# Battery_pack.net
KiCad netlist of a schematic drawn in EAGLE
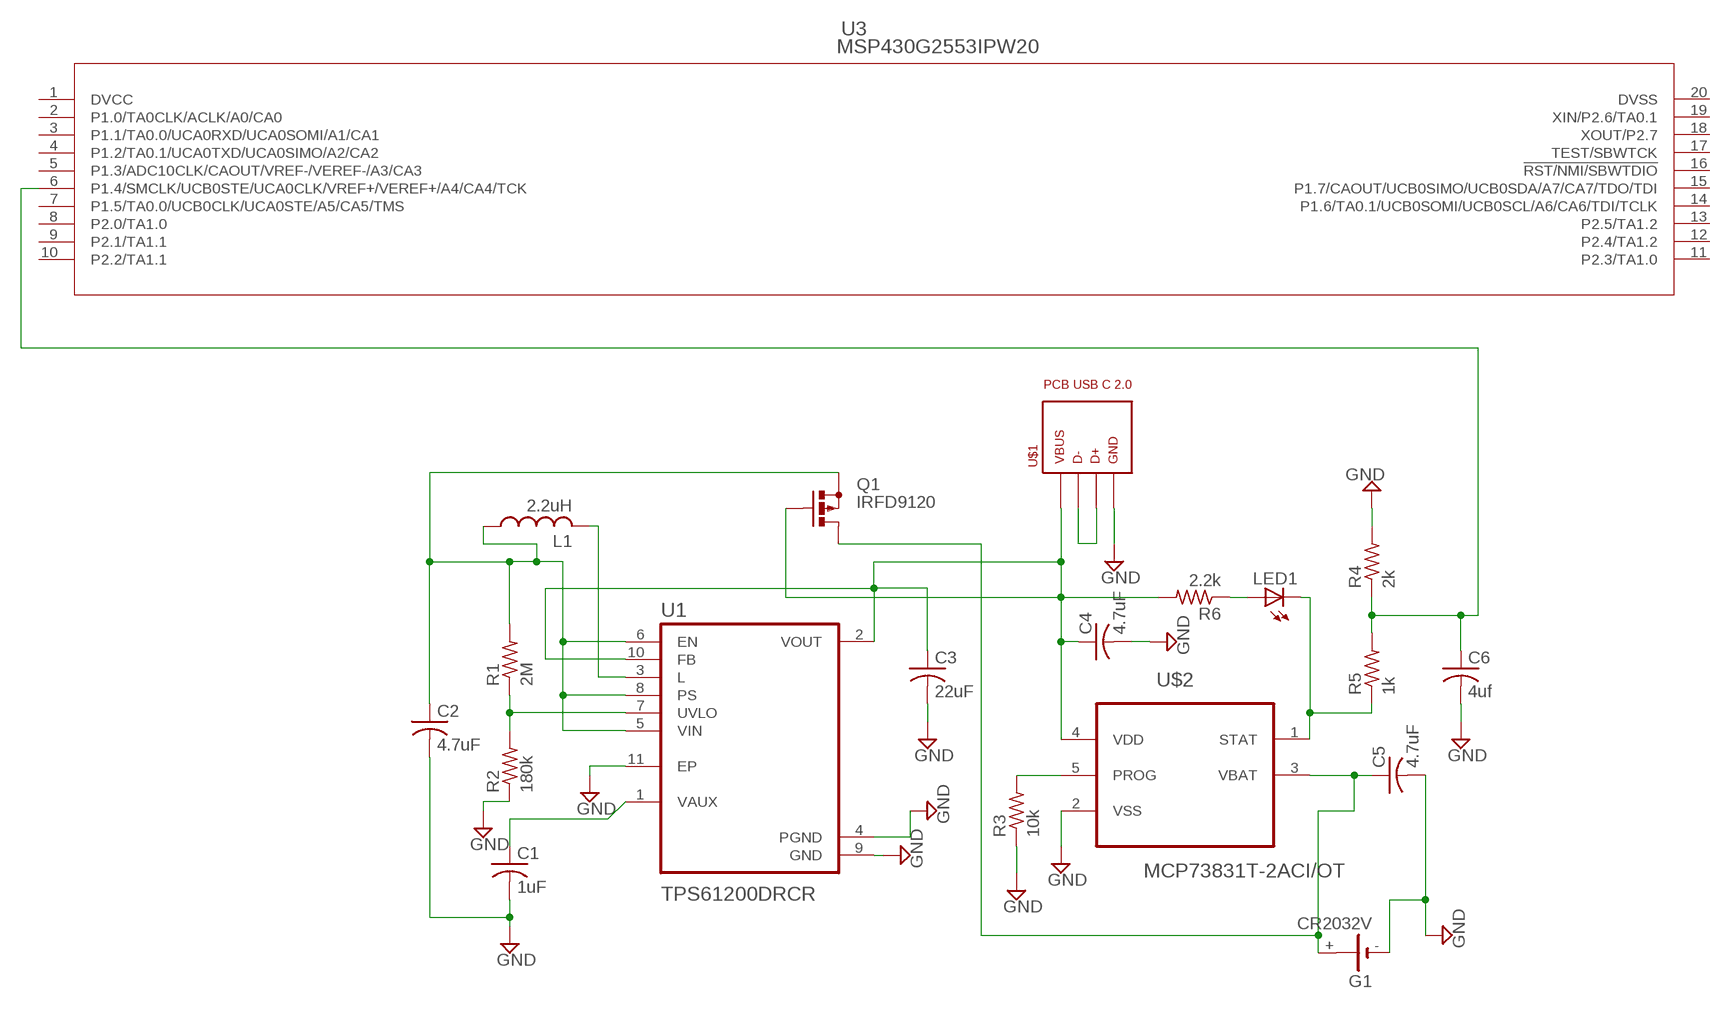
[diagram p0: schematic, sheet 1]

(export (version "E")
  (design (tool "Eeschema 10.0.6"))
  (components
    (comp (ref "C1")
      (value "1uF")
      (footprint "eagle-import:C150-064X183")
      (libsource (lib "eagle-import") (part "C-US150-064X183"))
    )
    (comp (ref "C2")
      (value "4.7uF")
      (footprint "eagle-import:C150-064X183")
      (libsource (lib "eagle-import") (part "C-US150-064X183"))
    )
    (comp (ref "C3")
      (value "22uF")
      (footprint "eagle-import:C150-064X183")
      (libsource (lib "eagle-import") (part "C-US150-064X183"))
    )
    (comp (ref "C4")
      (value "4.7uF")
      (footprint "eagle-import:C150-064X183")
      (libsource (lib "eagle-import") (part "C-US150-064X183"))
    )
    (comp (ref "C5")
      (value "4.7uF")
      (footprint "eagle-import:C150-064X183")
      (libsource (lib "eagle-import") (part "C-US150-064X183"))
    )
    (comp (ref "C6")
      (value "4uf")
      (footprint "eagle-import:C150-064X183")
      (libsource (lib "eagle-import") (part "C-US150-064X183"))
    )
    (comp (ref "G1")
      (value "CR2032V")
      (footprint "eagle-import:CR2032V")
      (libsource (lib "eagle-import") (part "CR2032V"))
    )
    (comp (ref "L1")
      (value "2.2uH")
      (footprint "eagle-import:0207_15")
      (libsource (lib "eagle-import") (part "L-US0207/15"))
    )
    (comp (ref "LED1")
      (value "LEDB155")
      (footprint "eagle-import:Q62902-B155")
      (libsource (lib "eagle-import") (part "LEDB155"))
    )
    (comp (ref "Q1")
      (value "IRFD9120")
      (footprint "eagle-import:C370-01")
      (libsource (lib "eagle-import") (part "IRFD9120"))
    )
    (comp (ref "R1")
      (value "2M")
      (footprint "eagle-import:0207_15")
      (libsource (lib "eagle-import") (part "R-US_0207/15"))
    )
    (comp (ref "R2")
      (value "180k")
      (footprint "eagle-import:0207_15")
      (libsource (lib "eagle-import") (part "R-US_0207/15"))
    )
    (comp (ref "R3")
      (value "10k")
      (footprint "eagle-import:0207_15")
      (libsource (lib "eagle-import") (part "R-US_0207/15"))
    )
    (comp (ref "R4")
      (value "2k")
      (footprint "eagle-import:0207_15")
      (libsource (lib "eagle-import") (part "R-US_0207/15"))
    )
    (comp (ref "R5")
      (value "1k")
      (footprint "eagle-import:0207_15")
      (libsource (lib "eagle-import") (part "R-US_0207/15"))
    )
    (comp (ref "R6")
      (value "2.2k")
      (footprint "eagle-import:0207_15")
      (libsource (lib "eagle-import") (part "R-US_0207/15"))
    )
    (comp (ref "U$1")
      (value "PCB_USB_C_2.0DS_1")
      (footprint "eagle-import:USB_TYPE_C_DS_1")
      (libsource (lib "eagle-import") (part "PCB_USB_C_2.0DS_1"))
    )
    (comp (ref "U$2")
      (value "MCP73831T-2ACI/OT")
      (footprint "eagle-import:SOT95P280X145-5N")
      (fields (field (name "MF") "Microchip"))
      (libsource (lib "eagle-import") (part "MCP73831T-2ACI/OT"))
    )
    (comp (ref "U1")
      (value "TPS61200DRCR")
      (footprint "eagle-import:VREG_V62_16624-01YE")
      (fields (field (name "MF") "Texas Instruments"))
      (libsource (lib "eagle-import") (part "TPS61200DRCR"))
    )
    (comp (ref "U3")
      (value "MSP430G2553IPW20")
      (footprint "eagle-import:PW20")
      (fields
        (field (name "GENERIC_PART_NUMBER") "MSP430G2553")
        (field (name "MANUFACTURER") "Texas Instruments")
      )
      (libsource (lib "eagle-import") (part "MSP430G2553IPW20"))
    )
  )
  (nets
    (net (code "1") (name "/DVCC") (class "Default")
      (node (ref "U3") (pin "1") (pinfunction "DVCC_1") (pintype "power_in"))
    )
    (net (code "2") (name "/DVSS") (class "Default")
      (node (ref "U3") (pin "20") (pinfunction "DVSS_20") (pintype "power_in"))
    )
    (net (code "3") (name "GND") (class "Default")
      (node (ref "C1") (pin "2") (pinfunction "2_2") (pintype "passive"))
      (node (ref "C2") (pin "2") (pinfunction "2_2") (pintype "passive"))
      (node (ref "C3") (pin "2") (pinfunction "2_2") (pintype "passive"))
      (node (ref "C4") (pin "2") (pinfunction "2_2") (pintype "passive"))
      (node (ref "C5") (pin "2") (pinfunction "2_2") (pintype "passive"))
      (node (ref "C6") (pin "2") (pinfunction "2_2") (pintype "passive"))
      (node (ref "G1") (pin "-") (pinfunction "-_-") (pintype "passive"))
      (node (ref "R2") (pin "1") (pinfunction "1_1") (pintype "passive"))
      (node (ref "R3") (pin "1") (pinfunction "1_1") (pintype "passive"))
      (node (ref "R4") (pin "2") (pinfunction "2_2") (pintype "passive"))
      (node (ref "U$1") (pin "A1") (pinfunction "GND_A1") (pintype "bidirectional"))
      (node (ref "U$1") (pin "A12") (pinfunction "GND_A12") (pintype "bidirectional"))
      (node (ref "U$1") (pin "B1") (pinfunction "GND_B1") (pintype "bidirectional"))
      (node (ref "U$1") (pin "B12") (pinfunction "GND_B12") (pintype "bidirectional"))
      (node (ref "U$2") (pin "2") (pinfunction "VSS_2") (pintype "power_in"))
      (node (ref "U1") (pin "11") (pinfunction "EP_11") (pintype "bidirectional"))
      (node (ref "U1") (pin "4") (pinfunction "PGND_4") (pintype "power_in"))
      (node (ref "U1") (pin "9") (pinfunction "GND_9") (pintype "power_in"))
    )
    (net (code "4") (name "Net-(LED1-C)") (class "Default")
      (node (ref "LED1") (pin "K") (pinfunction "C_K") (pintype "passive"))
      (node (ref "R5") (pin "1") (pinfunction "1_1") (pintype "passive"))
      (node (ref "U$2") (pin "1") (pinfunction "STAT_1") (pintype "output"))
    )
    (net (code "5") (name "Net-(LED1-PadA)") (class "Default")
      (node (ref "LED1") (pin "A") (pinfunction "A_A") (pintype "passive"))
      (node (ref "R6") (pin "1") (pinfunction "1_1") (pintype "passive"))
    )
    (net (code "6") (name "Net-(U$1-D+-PadA6)") (class "Default")
      (node (ref "U$1") (pin "A6") (pinfunction "D+_A6") (pintype "bidirectional"))
      (node (ref "U$1") (pin "A7") (pinfunction "D-_A7") (pintype "bidirectional"))
      (node (ref "U$1") (pin "B6") (pinfunction "D+_B6") (pintype "bidirectional"))
      (node (ref "U$1") (pin "B7") (pinfunction "D-_B7") (pintype "bidirectional"))
    )
    (net (code "7") (name "Net-(U$2-PROG)") (class "Default")
      (node (ref "R3") (pin "2") (pinfunction "2_2") (pintype "passive"))
      (node (ref "U$2") (pin "5") (pinfunction "PROG_5") (pintype "input"))
    )
    (net (code "8") (name "Net-(U$2-VBAT)") (class "Default")
      (node (ref "C5") (pin "1") (pinfunction "1_1") (pintype "passive"))
      (node (ref "G1") (pin "+") (pinfunction "+_+") (pintype "passive"))
      (node (ref "Q1") (pin "D") (pinfunction "D_D") (pintype "passive"))
      (node (ref "Q1") (pin "D1") (pinfunction "D_D1") (pintype "passive"))
      (node (ref "U$2") (pin "3") (pinfunction "VBAT_3") (pintype "output"))
    )
    (net (code "9") (name "Net-(U$2-VDD)") (class "Default")
      (node (ref "C3") (pin "1") (pinfunction "1_1") (pintype "passive"))
      (node (ref "C4") (pin "1") (pinfunction "1_1") (pintype "passive"))
      (node (ref "Q1") (pin "G") (pinfunction "G_G") (pintype "passive"))
      (node (ref "R6") (pin "2") (pinfunction "2_2") (pintype "passive"))
      (node (ref "U$1") (pin "A4") (pinfunction "VBUS_A4") (pintype "bidirectional"))
      (node (ref "U$1") (pin "A9") (pinfunction "VBUS_A9") (pintype "bidirectional"))
      (node (ref "U$1") (pin "B4") (pinfunction "VBUS_B4") (pintype "bidirectional"))
      (node (ref "U$1") (pin "B9") (pinfunction "VBUS_B9") (pintype "bidirectional"))
      (node (ref "U$2") (pin "4") (pinfunction "VDD_4") (pintype "power_in"))
      (node (ref "U1") (pin "10") (pinfunction "FB_10") (pintype "input"))
      (node (ref "U1") (pin "2") (pinfunction "VOUT_2") (pintype "output"))
    )
    (net (code "10") (name "Net-(U1-EN)") (class "Default")
      (node (ref "C2") (pin "1") (pinfunction "1_1") (pintype "passive"))
      (node (ref "L1") (pin "1") (pinfunction "1_1") (pintype "passive"))
      (node (ref "Q1") (pin "S") (pinfunction "S_S") (pintype "passive"))
      (node (ref "R1") (pin "2") (pinfunction "2_2") (pintype "passive"))
      (node (ref "U1") (pin "5") (pinfunction "VIN_5") (pintype "input"))
      (node (ref "U1") (pin "6") (pinfunction "EN_6") (pintype "input"))
      (node (ref "U1") (pin "8") (pinfunction "PS_8") (pintype "input"))
    )
    (net (code "11") (name "Net-(U1-L)") (class "Default")
      (node (ref "L1") (pin "2") (pinfunction "2_2") (pintype "passive"))
      (node (ref "U1") (pin "3") (pinfunction "L_3") (pintype "input"))
    )
    (net (code "12") (name "Net-(U1-UVLO)") (class "Default")
      (node (ref "R1") (pin "1") (pinfunction "1_1") (pintype "passive"))
      (node (ref "R2") (pin "2") (pinfunction "2_2") (pintype "passive"))
      (node (ref "U1") (pin "7") (pinfunction "UVLO_7") (pintype "input"))
    )
    (net (code "13") (name "Net-(U1-VAUX)") (class "Default")
      (node (ref "C1") (pin "1") (pinfunction "1_1") (pintype "passive"))
      (node (ref "U1") (pin "1") (pinfunction "VAUX_1") (pintype "bidirectional"))
    )
    (net (code "14") (name "Net-(U3-P1.4{slash}SMCLK{slash}UCB0STE{slash}UCA0CLK{slash}VREF+{slash}VEREF+{slash}A4{slash}CA4{slash}TCK)") (class "Default")
      (node (ref "C6") (pin "1") (pinfunction "1_1") (pintype "passive"))
      (node (ref "R4") (pin "1") (pinfunction "1_1") (pintype "passive"))
      (node (ref "R5") (pin "2") (pinfunction "2_2") (pintype "passive"))
      (node (ref "U3") (pin "6") (pinfunction "P1.4/SMCLK/UCB0STE/UCA0CLK/VREF+/VEREF+/A4/CA4/TCK_6") (pintype "bidirectional"))
    )
    (net (code "15") (name "unconnected-(G1-+-Pad+@1)") (class "Default")
      (node (ref "G1") (pin "+@1") (pinfunction "+_+@1") (pintype "passive"))
    )
    (net (code "16") (name "unconnected-(U3-P1.0{slash}TA0CLK{slash}ACLK{slash}A0{slash}CA0-Pad2)") (class "Default")
      (node (ref "U3") (pin "2") (pinfunction "P1.0/TA0CLK/ACLK/A0/CA0_2") (pintype "bidirectional"))
    )
    (net (code "17") (name "unconnected-(U3-P1.1{slash}TA0.0{slash}UCA0RXD{slash}UCA0SOMI{slash}A1{slash}CA1-Pad3)") (class "Default")
      (node (ref "U3") (pin "3") (pinfunction "P1.1/TA0.0/UCA0RXD/UCA0SOMI/A1/CA1_3") (pintype "bidirectional"))
    )
    (net (code "18") (name "unconnected-(U3-P1.2{slash}TA0.1{slash}UCA0TXD{slash}UCA0SIMO{slash}A2{slash}CA2-Pad4)") (class "Default")
      (node (ref "U3") (pin "4") (pinfunction "P1.2/TA0.1/UCA0TXD/UCA0SIMO/A2/CA2_4") (pintype "bidirectional"))
    )
    (net (code "19") (name "unconnected-(U3-P1.3{slash}ADC10CLK{slash}CAOUT{slash}VREF-{slash}VEREF-{slash}A3{slash}CA3-Pad5)") (class "Default")
      (node (ref "U3") (pin "5") (pinfunction "P1.3/ADC10CLK/CAOUT/VREF-/VEREF-/A3/CA3_5") (pintype "bidirectional"))
    )
    (net (code "20") (name "unconnected-(U3-P1.5{slash}TA0.0{slash}UCB0CLK{slash}UCA0STE{slash}A5{slash}CA5{slash}TMS-Pad7)") (class "Default")
      (node (ref "U3") (pin "7") (pinfunction "P1.5/TA0.0/UCB0CLK/UCA0STE/A5/CA5/TMS_7") (pintype "bidirectional"))
    )
    (net (code "21") (name "unconnected-(U3-P1.6{slash}TA0.1{slash}UCB0SOMI{slash}UCB0SCL{slash}A6{slash}CA6{slash}TDI{slash}TCLK-Pad14)") (class "Default")
      (node (ref "U3") (pin "14") (pinfunction "P1.6/TA0.1/UCB0SOMI/UCB0SCL/A6/CA6/TDI/TCLK_14") (pintype "bidirectional"))
    )
    (net (code "22") (name "unconnected-(U3-P1.7{slash}CAOUT{slash}UCB0SIMO{slash}UCB0SDA{slash}A7{slash}CA7{slash}TDO{slash}TDI-Pad15)") (class "Default")
      (node (ref "U3") (pin "15") (pinfunction "P1.7/CAOUT/UCB0SIMO/UCB0SDA/A7/CA7/TDO/TDI_15") (pintype "bidirectional"))
    )
    (net (code "23") (name "unconnected-(U3-P2.0{slash}TA1.0-Pad8)") (class "Default")
      (node (ref "U3") (pin "8") (pinfunction "P2.0/TA1.0_8") (pintype "bidirectional"))
    )
    (net (code "24") (name "unconnected-(U3-P2.1{slash}TA1.1-Pad9)") (class "Default")
      (node (ref "U3") (pin "9") (pinfunction "P2.1/TA1.1_9") (pintype "bidirectional"))
    )
    (net (code "25") (name "unconnected-(U3-P2.2{slash}TA1.1-Pad10)") (class "Default")
      (node (ref "U3") (pin "10") (pinfunction "P2.2/TA1.1_10") (pintype "bidirectional"))
    )
    (net (code "26") (name "unconnected-(U3-P2.3{slash}TA1.0-Pad11)") (class "Default")
      (node (ref "U3") (pin "11") (pinfunction "P2.3/TA1.0_11") (pintype "bidirectional"))
    )
    (net (code "27") (name "unconnected-(U3-P2.4{slash}TA1.2-Pad12)") (class "Default")
      (node (ref "U3") (pin "12") (pinfunction "P2.4/TA1.2_12") (pintype "bidirectional"))
    )
    (net (code "28") (name "unconnected-(U3-P2.5{slash}TA1.2-Pad13)") (class "Default")
      (node (ref "U3") (pin "13") (pinfunction "P2.5/TA1.2_13") (pintype "bidirectional"))
    )
    (net (code "29") (name "unconnected-(U3-TEST{slash}SBWTCK-Pad17)") (class "Default")
      (node (ref "U3") (pin "17") (pinfunction "TEST/SBWTCK_17") (pintype "bidirectional"))
    )
    (net (code "30") (name "unconnected-(U3-XIN{slash}P2.6{slash}TA0.1-Pad19)") (class "Default")
      (node (ref "U3") (pin "19") (pinfunction "XIN/P2.6/TA0.1_19") (pintype "bidirectional"))
    )
    (net (code "31") (name "unconnected-(U3-XOUT{slash}P2.7-Pad18)") (class "Default")
      (node (ref "U3") (pin "18") (pinfunction "XOUT/P2.7_18") (pintype "bidirectional"))
    )
    (net (code "32") (name "unconnected-(U3-~{RST{slash}NMI{slash}SBWTDIO}-Pad16)") (class "Default")
      (node (ref "U3") (pin "16") (pinfunction "~{RST/NMI/SBWTDIO}_16") (pintype "bidirectional"))
    )
  )
)
